# FTDI_Dynamixel_Board_2025.net
KiCad netlist of a schematic drawn in Altium Designer
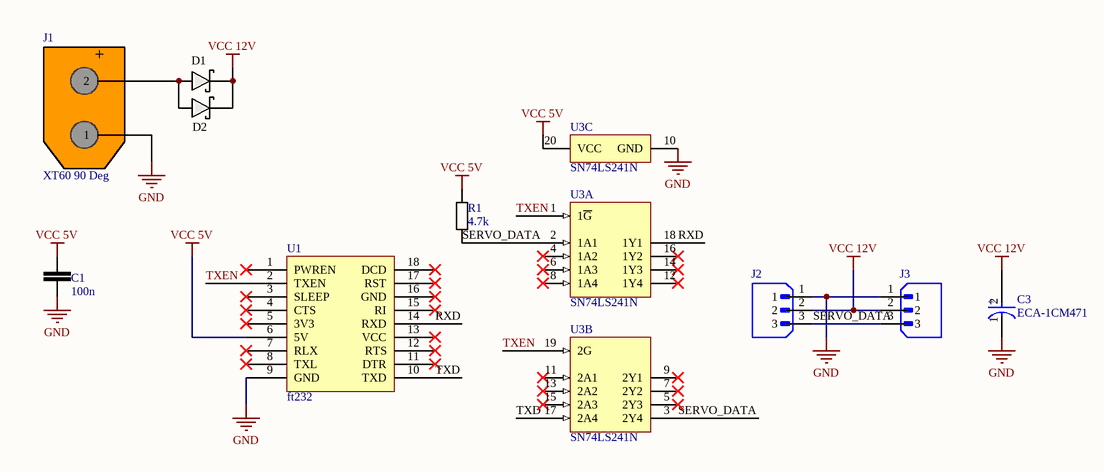
[diagram p0: FTDI_Dynamixel_Board_2025.SchDoc]

(export (version "E")
  (design (tool "Eeschema 10.0.6"))
  (components
    (comp (ref "C1")
      (value "100n")
      (footprint "CAP_0805")
      (description "CAP 100nF ±10% 50V 0805 X7R")
      (libsource (lib "Kondezatori_Integrisano") (part "C00079"))
    )
    (comp (ref "C3")
      (value "ECA-1CM471")
      (footprint "FP-ECA-1CM471-MFG")
      (description "CAP ALUM 470UF 20% 16V RADIAL")
      (fields (field (name "TOLERANCE") "20%") (field (name "VOLTAGE") "16V"))
      (libsource (lib "Altium Content Vault") (part "cf48714ba7e38822c1575c7ec0b6d1f"))
    )
    (comp (ref "D1") (value "SS14") (footprint "PcbLib2:SMA") (libsource (lib "Schlib") (part "SCH_DIODE")))
    (comp (ref "D2") (value "SS14") (footprint "PcbLib2:SMA") (libsource (lib "Schlib") (part "SCH_DIODE")))
    (comp (ref "J1")
      (value "XT60 90 Deg")
      (footprint "Connectors:XT60PW-M")
      (libsource (lib "Connectors") (part "XT60PW-M"))
    )
    (comp (ref "J2")
      (value "B3B-XH-A(LF)(SN)")
      (footprint "JST_B3B-XH-A(LF)(SN)")
      (description "Connector Header Through Hole 3 position 0.098 (2.50mm)")
      (fields (field (name "MF") "JST Sales"))
      (libsource (lib "") (part "B3B-XH-A(LF)(SN)_1"))
    )
    (comp (ref "J3")
      (value "B3B-XH-A(LF)(SN)")
      (footprint "JST_B3B-XH-A(LF)(SN)")
      (description "Connector Header Through Hole 3 position 0.098 (2.50mm)")
      (fields (field (name "MF") "JST Sales"))
      (libsource (lib "B3B-XH-A(LF)(SN)") (part "B3B-XH-A(LF)(SN)"))
    )
    (comp (ref "R1")
      (value "4.7k")
      (footprint "RESISTOR_0805_SMALLSILK")
      (description "RES  4k7 OHM 1% 1/8W 0805")
      (libsource (lib "Otpornici_Integrisano") (part "R000116"))
    )
    (comp (ref "U1")
      (value "ft232")
      (footprint "ft232modull")
      (libsource (lib "customMemristor") (part "ft232"))
    )
    (comp (ref "U3")
      (value "SN74LS241N")
      (footprint "N0020A")
      (description "Octal Buffers And Line Drivers With 3-State Outputs, N0020A, TUBE")
      (fields
        (field (name "GENERIC PART NUMBER") "SN74LS241")
        (field (name "MANUFACTURER") "Texas Instruments")
      )
      (libsource (lib "Altium Content Vault") (part "TI-SN74LS_74S241-20"))
    )
  )
  (nets
    (net (code "1") (name "/RXD") (class "Default")
      (node (ref "U1") (pin "14") (pinfunction "RXD_14") (pintype "passive"))
      (node (ref "U3") (pin "18") (pinfunction "1Y1_18") (pintype "tri_state"))
    )
    (net (code "2") (name "/SERVO_DATA") (class "Default")
      (node (ref "J2") (pin "3") (pinfunction "3_3") (pintype "passive"))
      (node (ref "J3") (pin "3") (pinfunction "3_3") (pintype "passive"))
      (node (ref "R1") (pin "1") (pinfunction "1_1") (pintype "passive"))
      (node (ref "U3") (pin "2") (pinfunction "1A1_2") (pintype "input"))
      (node (ref "U3") (pin "3") (pinfunction "2Y4_3") (pintype "tri_state"))
    )
    (net (code "3") (name "/TXD") (class "Default")
      (node (ref "U1") (pin "10") (pinfunction "TXD_10") (pintype "passive"))
      (node (ref "U3") (pin "17") (pinfunction "2A4_17") (pintype "input"))
    )
    (net (code "4") (name "/TXEN") (class "Default")
      (node (ref "U1") (pin "2") (pinfunction "TXEN_2") (pintype "passive"))
      (node (ref "U3") (pin "1") (pinfunction "1~{G}_1") (pintype "input"))
      (node (ref "U3") (pin "19") (pinfunction "2G_19") (pintype "input"))
    )
    (net (code "5") (name "GND") (class "Default")
      (node (ref "C1") (pin "1") (pinfunction "1_1") (pintype "passive"))
      (node (ref "C3") (pin "1") (pinfunction "C_1") (pintype "passive"))
      (node (ref "J1") (pin "1") (pinfunction "1_1") (pintype "passive"))
      (node (ref "J2") (pin "1") (pinfunction "1_1") (pintype "passive"))
      (node (ref "J3") (pin "1") (pinfunction "1_1") (pintype "passive"))
      (node (ref "U1") (pin "9") (pinfunction "GND_9") (pintype "passive"))
      (node (ref "U3") (pin "10") (pinfunction "GND_10") (pintype "power_in"))
    )
    (net (code "6") (name "Net-(D1-Pad1)") (class "Default")
      (node (ref "D1") (pin "1") (pinfunction "1_1") (pintype "passive"))
      (node (ref "D2") (pin "1") (pinfunction "1_1") (pintype "passive"))
      (node (ref "J1") (pin "2") (pinfunction "2_2") (pintype "passive"))
    )
    (net (code "7") (name "VCC 5V") (class "Default")
      (node (ref "C1") (pin "2") (pinfunction "2_2") (pintype "passive"))
      (node (ref "R1") (pin "2") (pinfunction "2_2") (pintype "passive"))
      (node (ref "U1") (pin "6") (pinfunction "5V_6") (pintype "passive"))
      (node (ref "U3") (pin "20") (pinfunction "VCC_20") (pintype "power_in"))
    )
    (net (code "8") (name "VCC 12V") (class "Default")
      (node (ref "C3") (pin "2") (pinfunction "A_2") (pintype "passive"))
      (node (ref "D1") (pin "2") (pinfunction "2_2") (pintype "passive"))
      (node (ref "D2") (pin "2") (pinfunction "2_2") (pintype "passive"))
      (node (ref "J2") (pin "2") (pinfunction "2_2") (pintype "passive"))
      (node (ref "J3") (pin "2") (pinfunction "2_2") (pintype "passive"))
    )
    (net (code "9") (name "unconnected-(U1-3V3-Pad5)") (class "Default")
      (node (ref "U1") (pin "5") (pinfunction "3V3_5") (pintype "passive+no_connect"))
    )
    (net (code "10") (name "unconnected-(U1-CTS-Pad4)") (class "Default")
      (node (ref "U1") (pin "4") (pinfunction "CTS_4") (pintype "passive+no_connect"))
    )
    (net (code "11") (name "unconnected-(U1-DCD-Pad18)") (class "Default")
      (node (ref "U1") (pin "18") (pinfunction "DCD_18") (pintype "passive+no_connect"))
    )
    (net (code "12") (name "unconnected-(U1-DTR-Pad11)") (class "Default")
      (node (ref "U1") (pin "11") (pinfunction "DTR_11") (pintype "passive+no_connect"))
    )
    (net (code "13") (name "unconnected-(U1-GND-Pad16)") (class "Default")
      (node (ref "U1") (pin "16") (pinfunction "GND_16") (pintype "passive+no_connect"))
    )
    (net (code "14") (name "unconnected-(U1-PWREN-Pad1)") (class "Default")
      (node (ref "U1") (pin "1") (pinfunction "PWREN_1") (pintype "passive+no_connect"))
    )
    (net (code "15") (name "unconnected-(U1-RI-Pad15)") (class "Default")
      (node (ref "U1") (pin "15") (pinfunction "RI_15") (pintype "passive+no_connect"))
    )
    (net (code "16") (name "unconnected-(U1-RLX-Pad7)") (class "Default")
      (node (ref "U1") (pin "7") (pinfunction "RLX_7") (pintype "passive+no_connect"))
    )
    (net (code "17") (name "unconnected-(U1-RST-Pad17)") (class "Default")
      (node (ref "U1") (pin "17") (pinfunction "RST_17") (pintype "passive+no_connect"))
    )
    (net (code "18") (name "unconnected-(U1-RTS-Pad12)") (class "Default")
      (node (ref "U1") (pin "12") (pinfunction "RTS_12") (pintype "passive+no_connect"))
    )
    (net (code "19") (name "unconnected-(U1-SLEEP-Pad3)") (class "Default")
      (node (ref "U1") (pin "3") (pinfunction "SLEEP_3") (pintype "passive+no_connect"))
    )
    (net (code "20") (name "unconnected-(U1-TXL-Pad8)") (class "Default")
      (node (ref "U1") (pin "8") (pinfunction "TXL_8") (pintype "passive+no_connect"))
    )
    (net (code "21") (name "unconnected-(U1-VCC-Pad13)") (class "Default")
      (node (ref "U1") (pin "13") (pinfunction "VCC_13") (pintype "passive+no_connect"))
    )
    (net (code "22") (name "unconnected-(U3A-1A2-Pad4)") (class "Default")
      (node (ref "U3") (pin "4") (pinfunction "1A2_4") (pintype "input+no_connect"))
    )
    (net (code "23") (name "unconnected-(U3A-1A3-Pad6)") (class "Default")
      (node (ref "U3") (pin "6") (pinfunction "1A3_6") (pintype "input+no_connect"))
    )
    (net (code "24") (name "unconnected-(U3A-1A4-Pad8)") (class "Default")
      (node (ref "U3") (pin "8") (pinfunction "1A4_8") (pintype "input+no_connect"))
    )
    (net (code "25") (name "unconnected-(U3A-1Y2-Pad16)") (class "Default")
      (node (ref "U3") (pin "16") (pinfunction "1Y2_16") (pintype "tri_state+no_connect"))
    )
    (net (code "26") (name "unconnected-(U3A-1Y3-Pad14)") (class "Default")
      (node (ref "U3") (pin "14") (pinfunction "1Y3_14") (pintype "tri_state+no_connect"))
    )
    (net (code "27") (name "unconnected-(U3A-1Y4-Pad12)") (class "Default")
      (node (ref "U3") (pin "12") (pinfunction "1Y4_12") (pintype "tri_state+no_connect"))
    )
    (net (code "28") (name "unconnected-(U3B-2A1-Pad11)") (class "Default")
      (node (ref "U3") (pin "11") (pinfunction "2A1_11") (pintype "input+no_connect"))
    )
    (net (code "29") (name "unconnected-(U3B-2A2-Pad13)") (class "Default")
      (node (ref "U3") (pin "13") (pinfunction "2A2_13") (pintype "input+no_connect"))
    )
    (net (code "30") (name "unconnected-(U3B-2A3-Pad15)") (class "Default")
      (node (ref "U3") (pin "15") (pinfunction "2A3_15") (pintype "input+no_connect"))
    )
    (net (code "31") (name "unconnected-(U3B-2Y1-Pad9)") (class "Default")
      (node (ref "U3") (pin "9") (pinfunction "2Y1_9") (pintype "tri_state+no_connect"))
    )
    (net (code "32") (name "unconnected-(U3B-2Y2-Pad7)") (class "Default")
      (node (ref "U3") (pin "7") (pinfunction "2Y2_7") (pintype "tri_state+no_connect"))
    )
    (net (code "33") (name "unconnected-(U3B-2Y3-Pad5)") (class "Default")
      (node (ref "U3") (pin "5") (pinfunction "2Y3_5") (pintype "tri_state+no_connect"))
    )
  )
)
